# 153-03D_LCNC_IO_expander.net
KiCad netlist of a schematic drawn in EAGLE
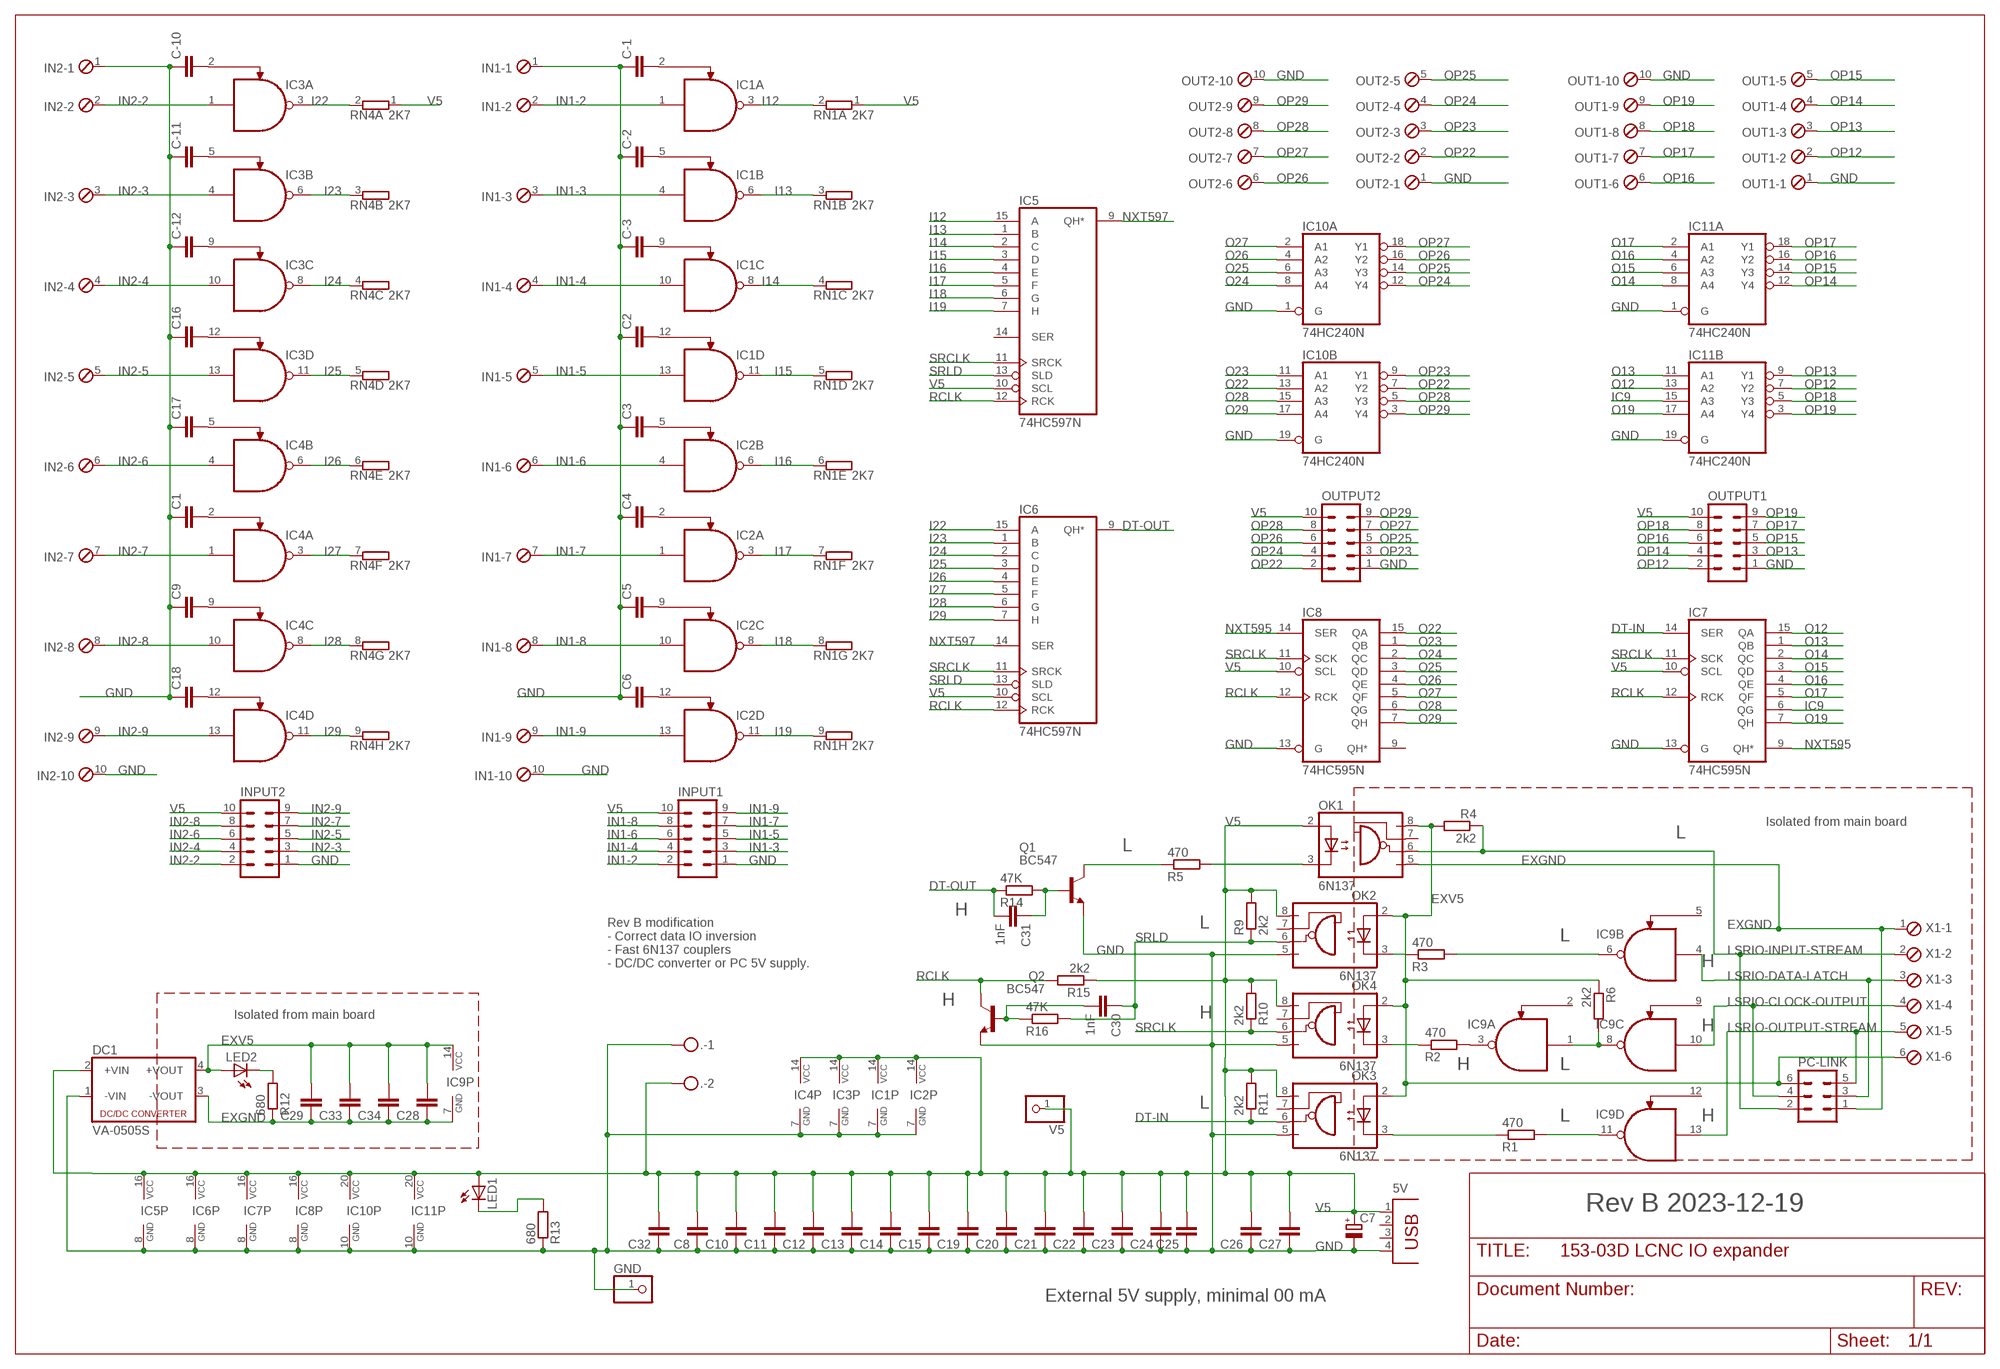
[diagram p0: schematic, sheet 1]

(export (version "E")
  (design (tool "Eeschema 10.0.6"))
  (components
    (comp (ref ".")
      (value "MKDSN1,5/2-5,08")
      (footprint "eagle-import:MKDSN1,5_2-5,08")
      (libsource (lib "eagle-import") (part "MKDSN1,5/2-5,08"))
    )
    (comp (ref "5V")
      (value "PN87520")
      (footprint "eagle-import:PN87520")
      (libsource (lib "eagle-import") (part "PN87520"))
    )
    (comp (ref "C-1")
      (value "C-EU025-024X044")
      (footprint "eagle-import:C025-024X044")
      (libsource (lib "eagle-import") (part "C-EU025-024X044"))
    )
    (comp (ref "C-2")
      (value "C-EU025-024X044")
      (footprint "eagle-import:C025-024X044")
      (libsource (lib "eagle-import") (part "C-EU025-024X044"))
    )
    (comp (ref "C-3")
      (value "C-EU025-024X044")
      (footprint "eagle-import:C025-024X044")
      (libsource (lib "eagle-import") (part "C-EU025-024X044"))
    )
    (comp (ref "C-10")
      (value "C-EU025-024X044")
      (footprint "eagle-import:C025-024X044")
      (libsource (lib "eagle-import") (part "C-EU025-024X044"))
    )
    (comp (ref "C-11")
      (value "C-EU025-024X044")
      (footprint "eagle-import:C025-024X044")
      (libsource (lib "eagle-import") (part "C-EU025-024X044"))
    )
    (comp (ref "C-12")
      (value "C-EU025-024X044")
      (footprint "eagle-import:C025-024X044")
      (libsource (lib "eagle-import") (part "C-EU025-024X044"))
    )
    (comp (ref "C1")
      (value "C-EU025-024X044")
      (footprint "eagle-import:C025-024X044")
      (libsource (lib "eagle-import") (part "C-EU025-024X044"))
    )
    (comp (ref "C2")
      (value "C-EU025-024X044")
      (footprint "eagle-import:C025-024X044")
      (libsource (lib "eagle-import") (part "C-EU025-024X044"))
    )
    (comp (ref "C3")
      (value "C-EU025-024X044")
      (footprint "eagle-import:C025-024X044")
      (libsource (lib "eagle-import") (part "C-EU025-024X044"))
    )
    (comp (ref "C4")
      (value "C-EU025-024X044")
      (footprint "eagle-import:C025-024X044")
      (libsource (lib "eagle-import") (part "C-EU025-024X044"))
    )
    (comp (ref "C5")
      (value "C-EU025-024X044")
      (footprint "eagle-import:C025-024X044")
      (libsource (lib "eagle-import") (part "C-EU025-024X044"))
    )
    (comp (ref "C6")
      (value "C-EU025-024X044")
      (footprint "eagle-import:C025-024X044")
      (libsource (lib "eagle-import") (part "C-EU025-024X044"))
    )
    (comp (ref "C7")
      (value "CPOL-EUE3.5-8")
      (footprint "eagle-import:E3,5-8")
      (libsource (lib "eagle-import") (part "CPOL-EUE3.5-8"))
    )
    (comp (ref "C8")
      (value "C-EU025-024X044")
      (footprint "eagle-import:C025-024X044")
      (libsource (lib "eagle-import") (part "C-EU025-024X044"))
    )
    (comp (ref "C9")
      (value "C-EU025-024X044")
      (footprint "eagle-import:C025-024X044")
      (libsource (lib "eagle-import") (part "C-EU025-024X044"))
    )
    (comp (ref "C10")
      (value "C-EU025-024X044")
      (footprint "eagle-import:C025-024X044")
      (libsource (lib "eagle-import") (part "C-EU025-024X044"))
    )
    (comp (ref "C11")
      (value "C-EU025-024X044")
      (footprint "eagle-import:C025-024X044")
      (libsource (lib "eagle-import") (part "C-EU025-024X044"))
    )
    (comp (ref "C12")
      (value "C-EU025-024X044")
      (footprint "eagle-import:C025-024X044")
      (libsource (lib "eagle-import") (part "C-EU025-024X044"))
    )
    (comp (ref "C13")
      (value "C-EU025-024X044")
      (footprint "eagle-import:C025-024X044")
      (libsource (lib "eagle-import") (part "C-EU025-024X044"))
    )
    (comp (ref "C14")
      (value "C-EU025-024X044")
      (footprint "eagle-import:C025-024X044")
      (libsource (lib "eagle-import") (part "C-EU025-024X044"))
    )
    (comp (ref "C15")
      (value "C-EU025-024X044")
      (footprint "eagle-import:C025-024X044")
      (libsource (lib "eagle-import") (part "C-EU025-024X044"))
    )
    (comp (ref "C16")
      (value "C-EU025-024X044")
      (footprint "eagle-import:C025-024X044")
      (libsource (lib "eagle-import") (part "C-EU025-024X044"))
    )
    (comp (ref "C17")
      (value "C-EU025-024X044")
      (footprint "eagle-import:C025-024X044")
      (libsource (lib "eagle-import") (part "C-EU025-024X044"))
    )
    (comp (ref "C18")
      (value "C-EU025-024X044")
      (footprint "eagle-import:C025-024X044")
      (libsource (lib "eagle-import") (part "C-EU025-024X044"))
    )
    (comp (ref "C19")
      (value "C-EU025-024X044")
      (footprint "eagle-import:C025-024X044")
      (libsource (lib "eagle-import") (part "C-EU025-024X044"))
    )
    (comp (ref "C20")
      (value "C-EU025-024X044")
      (footprint "eagle-import:C025-024X044")
      (libsource (lib "eagle-import") (part "C-EU025-024X044"))
    )
    (comp (ref "C21")
      (value "C-EU025-024X044")
      (footprint "eagle-import:C025-024X044")
      (libsource (lib "eagle-import") (part "C-EU025-024X044"))
    )
    (comp (ref "C22")
      (value "C-EU025-024X044")
      (footprint "eagle-import:C025-024X044")
      (libsource (lib "eagle-import") (part "C-EU025-024X044"))
    )
    (comp (ref "C23")
      (value "C-EU025-024X044")
      (footprint "eagle-import:C025-024X044")
      (libsource (lib "eagle-import") (part "C-EU025-024X044"))
    )
    (comp (ref "C24")
      (value "C-EU025-024X044")
      (footprint "eagle-import:C025-024X044")
      (libsource (lib "eagle-import") (part "C-EU025-024X044"))
    )
    (comp (ref "C25")
      (value "C-EU025-024X044")
      (footprint "eagle-import:C025-024X044")
      (libsource (lib "eagle-import") (part "C-EU025-024X044"))
    )
    (comp (ref "C26")
      (value "C-EU025-024X044")
      (footprint "eagle-import:C025-024X044")
      (libsource (lib "eagle-import") (part "C-EU025-024X044"))
    )
    (comp (ref "C27")
      (value "C-EU025-024X044")
      (footprint "eagle-import:C025-024X044")
      (libsource (lib "eagle-import") (part "C-EU025-024X044"))
    )
    (comp (ref "C28")
      (value "C-EU025-024X044")
      (footprint "eagle-import:C025-024X044")
      (libsource (lib "eagle-import") (part "C-EU025-024X044"))
    )
    (comp (ref "C29")
      (value "C-EU025-024X044")
      (footprint "eagle-import:C025-024X044")
      (libsource (lib "eagle-import") (part "C-EU025-024X044"))
    )
    (comp (ref "C30")
      (value "1nF")
      (footprint "eagle-import:C025-024X044")
      (libsource (lib "eagle-import") (part "C-EU025-024X044"))
    )
    (comp (ref "C31")
      (value "1nF")
      (footprint "eagle-import:C025-024X044")
      (libsource (lib "eagle-import") (part "C-EU025-024X044"))
    )
    (comp (ref "C32")
      (value "C-EU025-024X044")
      (footprint "eagle-import:C025-024X044")
      (libsource (lib "eagle-import") (part "C-EU025-024X044"))
    )
    (comp (ref "C33")
      (value "C-EU025-024X044")
      (footprint "eagle-import:C025-024X044")
      (libsource (lib "eagle-import") (part "C-EU025-024X044"))
    )
    (comp (ref "C34")
      (value "C-EU025-024X044")
      (footprint "eagle-import:C025-024X044")
      (libsource (lib "eagle-import") (part "C-EU025-024X044"))
    )
    (comp (ref "DC1")
      (value "VA-0505S")
      (footprint "eagle-import:4SIL")
      (libsource (lib "eagle-import") (part "VA-?S0505"))
    )
    (comp (ref "GND")
      (value "PINHD-1X1")
      (footprint "eagle-import:1X01")
      (libsource (lib "eagle-import") (part "PINHD-1X1"))
    )
    (comp (ref "IC1")
      (value "MC1489DIP")
      (footprint "eagle-import:DIL14")
      (libsource (lib "eagle-import") (part "MC1489DIP"))
    )
    (comp (ref "IC2")
      (value "MC1489DIP")
      (footprint "eagle-import:DIL14")
      (libsource (lib "eagle-import") (part "MC1489DIP"))
    )
    (comp (ref "IC3")
      (value "MC1489DIP")
      (footprint "eagle-import:DIL14")
      (libsource (lib "eagle-import") (part "MC1489DIP"))
    )
    (comp (ref "IC4")
      (value "MC1489DIP")
      (footprint "eagle-import:DIL14")
      (libsource (lib "eagle-import") (part "MC1489DIP"))
    )
    (comp (ref "IC5")
      (value "74HC597N")
      (footprint "eagle-import:DIL16")
      (libsource (lib "eagle-import") (part "74597NHC"))
    )
    (comp (ref "IC6")
      (value "74HC597N")
      (footprint "eagle-import:DIL16")
      (libsource (lib "eagle-import") (part "74597NHC"))
    )
    (comp (ref "IC7")
      (value "74HC595N")
      (footprint "eagle-import:DIL16")
      (libsource (lib "eagle-import") (part "74595NHC"))
    )
    (comp (ref "IC8")
      (value "74HC595N")
      (footprint "eagle-import:DIL16")
      (libsource (lib "eagle-import") (part "74595NHC"))
    )
    (comp (ref "IC9")
      (value "MC1489DIP")
      (footprint "eagle-import:DIL14")
      (libsource (lib "eagle-import") (part "MC1489DIP"))
    )
    (comp (ref "IC10")
      (value "74HC240N")
      (footprint "eagle-import:DIL20")
      (libsource (lib "eagle-import") (part "74240NHC"))
    )
    (comp (ref "IC11")
      (value "74HC240N")
      (footprint "eagle-import:DIL20")
      (libsource (lib "eagle-import") (part "74240NHC"))
    )
    (comp (ref "IN1")
      (value "MPT10")
      (footprint "eagle-import:10POL254")
      (libsource (lib "eagle-import") (part "MPT10"))
    )
    (comp (ref "IN2")
      (value "MPT10")
      (footprint "eagle-import:10POL254")
      (libsource (lib "eagle-import") (part "MPT10"))
    )
    (comp (ref "INPUT1")
      (value "ML10")
      (footprint "eagle-import:ML10")
      (libsource (lib "eagle-import") (part "ML10"))
    )
    (comp (ref "INPUT2")
      (value "ML10")
      (footprint "eagle-import:ML10")
      (libsource (lib "eagle-import") (part "ML10"))
    )
    (comp (ref "LED1")
      (value "LED3MM")
      (footprint "eagle-import:LED3MM")
      (libsource (lib "eagle-import") (part "LED3MM"))
    )
    (comp (ref "LED2")
      (value "LED3MM")
      (footprint "eagle-import:LED3MM")
      (libsource (lib "eagle-import") (part "LED3MM"))
    )
    (comp (ref "OK1")
      (value "6N137")
      (footprint "eagle-import:DIL08")
      (libsource (lib "eagle-import") (part "6N137"))
    )
    (comp (ref "OK2")
      (value "6N137")
      (footprint "eagle-import:DIL08")
      (libsource (lib "eagle-import") (part "6N137"))
    )
    (comp (ref "OK3")
      (value "6N137")
      (footprint "eagle-import:DIL08")
      (libsource (lib "eagle-import") (part "6N137"))
    )
    (comp (ref "OK4")
      (value "6N137")
      (footprint "eagle-import:DIL08")
      (libsource (lib "eagle-import") (part "6N137"))
    )
    (comp (ref "OUT1")
      (value "MPT10")
      (footprint "eagle-import:10POL254")
      (libsource (lib "eagle-import") (part "MPT10"))
    )
    (comp (ref "OUT2")
      (value "MPT10")
      (footprint "eagle-import:10POL254")
      (libsource (lib "eagle-import") (part "MPT10"))
    )
    (comp (ref "OUTPUT1")
      (value "ML10")
      (footprint "eagle-import:ML10")
      (libsource (lib "eagle-import") (part "ML10"))
    )
    (comp (ref "OUTPUT2")
      (value "ML10")
      (footprint "eagle-import:ML10")
      (libsource (lib "eagle-import") (part "ML10"))
    )
    (comp (ref "PC-LINK")
      (value "ML6")
      (footprint "eagle-import:ML6")
      (libsource (lib "eagle-import") (part "ML6"))
    )
    (comp (ref "Q1")
      (value "BC547")
      (footprint "eagle-import:TO92")
      (libsource (lib "eagle-import") (part "BC547"))
    )
    (comp (ref "Q2")
      (value "BC547")
      (footprint "eagle-import:TO92")
      (libsource (lib "eagle-import") (part "BC547"))
    )
    (comp (ref "R1")
      (value "470")
      (footprint "eagle-import:0207_10")
      (libsource (lib "eagle-import") (part "R-EU_0207/10"))
    )
    (comp (ref "R2")
      (value "470")
      (footprint "eagle-import:0207_10")
      (libsource (lib "eagle-import") (part "R-EU_0207/10"))
    )
    (comp (ref "R3")
      (value "470")
      (footprint "eagle-import:0207_10")
      (libsource (lib "eagle-import") (part "R-EU_0207/10"))
    )
    (comp (ref "R4")
      (value "2k2")
      (footprint "eagle-import:0207_10")
      (libsource (lib "eagle-import") (part "R-EU_0207/10"))
    )
    (comp (ref "R5")
      (value "470")
      (footprint "eagle-import:0207_10")
      (libsource (lib "eagle-import") (part "R-EU_0207/10"))
    )
    (comp (ref "R6")
      (value "2k2")
      (footprint "eagle-import:0207_10")
      (libsource (lib "eagle-import") (part "R-EU_0207/10"))
    )
    (comp (ref "R9")
      (value "2k2")
      (footprint "eagle-import:0207_10")
      (libsource (lib "eagle-import") (part "R-EU_0207/10"))
    )
    (comp (ref "R10")
      (value "2k2")
      (footprint "eagle-import:0207_10")
      (libsource (lib "eagle-import") (part "R-EU_0207/10"))
    )
    (comp (ref "R11")
      (value "2k2")
      (footprint "eagle-import:0207_10")
      (libsource (lib "eagle-import") (part "R-EU_0207/10"))
    )
    (comp (ref "R12")
      (value "680")
      (footprint "eagle-import:0207_10")
      (libsource (lib "eagle-import") (part "R-EU_0207/10"))
    )
    (comp (ref "R13")
      (value "680")
      (footprint "eagle-import:0207_10")
      (libsource (lib "eagle-import") (part "R-EU_0207/10"))
    )
    (comp (ref "R14")
      (value "47K")
      (footprint "eagle-import:0207_10")
      (libsource (lib "eagle-import") (part "R-EU_0207/10"))
    )
    (comp (ref "R15")
      (value "2k2")
      (footprint "eagle-import:0207_10")
      (libsource (lib "eagle-import") (part "R-EU_0207/10"))
    )
    (comp (ref "R16")
      (value "47K")
      (footprint "eagle-import:0207_10")
      (libsource (lib "eagle-import") (part "R-EU_0207/10"))
    )
    (comp (ref "RN1")
      (value "2K7")
      (footprint "eagle-import:SIL9")
      (libsource (lib "eagle-import") (part "GE08R"))
    )
    (comp (ref "RN4")
      (value "2K7")
      (footprint "eagle-import:SIL9")
      (libsource (lib "eagle-import") (part "GE08R"))
    )
    (comp (ref "V5")
      (value "PINHD-1X1")
      (footprint "eagle-import:1X01")
      (libsource (lib "eagle-import") (part "PINHD-1X1"))
    )
    (comp (ref "X1")
      (value "MPT6")
      (footprint "eagle-import:6POL254")
      (libsource (lib "eagle-import") (part "MPT6"))
    )
  )
  (nets
    (net (code "1") (name "/DT-IN") (class "Default")
      (node (ref "IC7") (pin "14") (pinfunction "SER_14") (pintype "input"))
      (node (ref "OK3") (pin "6") (pinfunction "VO_6") (pintype "passive"))
      (node (ref "R11") (pin "1") (pinfunction "1_1") (pintype "passive"))
    )
    (net (code "2") (name "/DT-OUT") (class "Default")
      (node (ref "C31") (pin "2") (pinfunction "2_2") (pintype "passive"))
      (node (ref "IC6") (pin "9") (pinfunction "QH*_9") (pintype "output"))
      (node (ref "R14") (pin "1") (pinfunction "1_1") (pintype "passive"))
    )
    (net (code "3") (name "/EXGND") (class "Default")
      (node (ref "C28") (pin "1") (pinfunction "1_1") (pintype "passive"))
      (node (ref "C29") (pin "1") (pinfunction "1_1") (pintype "passive"))
      (node (ref "C33") (pin "1") (pinfunction "1_1") (pintype "passive"))
      (node (ref "C34") (pin "1") (pinfunction "1_1") (pintype "passive"))
      (node (ref "DC1") (pin "3") (pinfunction "-VOUT_3") (pintype "passive"))
      (node (ref "IC9") (pin "7") (pinfunction "GND_7") (pintype "power_in"))
      (node (ref "OK1") (pin "5") (pinfunction "GND_5") (pintype "passive"))
      (node (ref "PC-LINK") (pin "1") (pinfunction "1_1") (pintype "passive"))
      (node (ref "R12") (pin "1") (pinfunction "1_1") (pintype "passive"))
      (node (ref "X1") (pin "1") (pinfunction "1_1") (pintype "passive"))
    )
    (net (code "4") (name "/EXV5") (class "Default")
      (node (ref "C28") (pin "2") (pinfunction "2_2") (pintype "passive"))
      (node (ref "C29") (pin "2") (pinfunction "2_2") (pintype "passive"))
      (node (ref "C33") (pin "2") (pinfunction "2_2") (pintype "passive"))
      (node (ref "C34") (pin "2") (pinfunction "2_2") (pintype "passive"))
      (node (ref "DC1") (pin "4") (pinfunction "+VOUT_4") (pintype "passive"))
      (node (ref "IC9") (pin "14") (pinfunction "VCC_14") (pintype "power_in"))
      (node (ref "LED2") (pin "A") (pinfunction "A_A") (pintype "passive"))
      (node (ref "OK1") (pin "8") (pinfunction "VCC_8") (pintype "passive"))
      (node (ref "OK2") (pin "2") (pinfunction "A_2") (pintype "passive"))
      (node (ref "OK3") (pin "2") (pinfunction "A_2") (pintype "passive"))
      (node (ref "OK4") (pin "2") (pinfunction "A_2") (pintype "passive"))
      (node (ref "PC-LINK") (pin "6") (pinfunction "6_6") (pintype "passive"))
      (node (ref "R4") (pin "2") (pinfunction "2_2") (pintype "passive"))
      (node (ref "R6") (pin "1") (pinfunction "1_1") (pintype "passive"))
      (node (ref "X1") (pin "6") (pinfunction "1_6") (pintype "passive"))
    )
    (net (code "5") (name "/GND") (class "Default")
      (node (ref ".") (pin "1") (pinfunction "KL_1") (pintype "passive"))
      (node (ref "5V") (pin "4") (pinfunction "4_4") (pintype "passive"))
      (node (ref "C-1") (pin "1") (pinfunction "1_1") (pintype "passive"))
      (node (ref "C-10") (pin "1") (pinfunction "1_1") (pintype "passive"))
      (node (ref "C-11") (pin "1") (pinfunction "1_1") (pintype "passive"))
      (node (ref "C-12") (pin "1") (pinfunction "1_1") (pintype "passive"))
      (node (ref "C-2") (pin "1") (pinfunction "1_1") (pintype "passive"))
      (node (ref "C-3") (pin "1") (pinfunction "1_1") (pintype "passive"))
      (node (ref "C1") (pin "1") (pinfunction "1_1") (pintype "passive"))
      (node (ref "C10") (pin "1") (pinfunction "1_1") (pintype "passive"))
      (node (ref "C11") (pin "1") (pinfunction "1_1") (pintype "passive"))
      (node (ref "C12") (pin "1") (pinfunction "1_1") (pintype "passive"))
      (node (ref "C13") (pin "1") (pinfunction "1_1") (pintype "passive"))
      (node (ref "C14") (pin "1") (pinfunction "1_1") (pintype "passive"))
      (node (ref "C15") (pin "1") (pinfunction "1_1") (pintype "passive"))
      (node (ref "C16") (pin "1") (pinfunction "1_1") (pintype "passive"))
      (node (ref "C17") (pin "1") (pinfunction "1_1") (pintype "passive"))
      (node (ref "C18") (pin "1") (pinfunction "1_1") (pintype "passive"))
      (node (ref "C19") (pin "1") (pinfunction "1_1") (pintype "passive"))
      (node (ref "C2") (pin "1") (pinfunction "1_1") (pintype "passive"))
      (node (ref "C20") (pin "1") (pinfunction "1_1") (pintype "passive"))
      (node (ref "C21") (pin "1") (pinfunction "1_1") (pintype "passive"))
      (node (ref "C22") (pin "1") (pinfunction "1_1") (pintype "passive"))
      (node (ref "C23") (pin "1") (pinfunction "1_1") (pintype "passive"))
      (node (ref "C24") (pin "1") (pinfunction "1_1") (pintype "passive"))
      (node (ref "C25") (pin "1") (pinfunction "1_1") (pintype "passive"))
      (node (ref "C26") (pin "1") (pinfunction "1_1") (pintype "passive"))
      (node (ref "C27") (pin "1") (pinfunction "1_1") (pintype "passive"))
      (node (ref "C3") (pin "1") (pinfunction "1_1") (pintype "passive"))
      (node (ref "C32") (pin "1") (pinfunction "1_1") (pintype "passive"))
      (node (ref "C4") (pin "1") (pinfunction "1_1") (pintype "passive"))
      (node (ref "C5") (pin "1") (pinfunction "1_1") (pintype "passive"))
      (node (ref "C6") (pin "1") (pinfunction "1_1") (pintype "passive"))
      (node (ref "C7") (pin "-") (pinfunction "-_-") (pintype "passive"))
      (node (ref "C8") (pin "1") (pinfunction "1_1") (pintype "passive"))
      (node (ref "C9") (pin "1") (pinfunction "1_1") (pintype "passive"))
      (node (ref "DC1") (pin "1") (pinfunction "-VIN_1") (pintype "passive"))
      (node (ref "GND") (pin "1") (pinfunction "1_1") (pintype "passive"))
      (node (ref "IC1") (pin "7") (pinfunction "GND_7") (pintype "power_in"))
      (node (ref "IC10") (pin "1") (pinfunction "G_1") (pintype "input"))
      (node (ref "IC10") (pin "10") (pinfunction "GND_10") (pintype "power_in"))
      (node (ref "IC10") (pin "19") (pinfunction "G_19") (pintype "input"))
      (node (ref "IC11") (pin "1") (pinfunction "G_1") (pintype "input"))
      (node (ref "IC11") (pin "10") (pinfunction "GND_10") (pintype "power_in"))
      (node (ref "IC11") (pin "19") (pinfunction "G_19") (pintype "input"))
      (node (ref "IC2") (pin "7") (pinfunction "GND_7") (pintype "power_in"))
      (node (ref "IC3") (pin "7") (pinfunction "GND_7") (pintype "power_in"))
      (node (ref "IC4") (pin "7") (pinfunction "GND_7") (pintype "power_in"))
      (node (ref "IC5") (pin "8") (pinfunction "GND_8") (pintype "power_in"))
      (node (ref "IC6") (pin "8") (pinfunction "GND_8") (pintype "power_in"))
      (node (ref "IC7") (pin "13") (pinfunction "G_13") (pintype "input"))
      (node (ref "IC7") (pin "8") (pinfunction "GND_8") (pintype "power_in"))
      (node (ref "IC8") (pin "13") (pinfunction "G_13") (pintype "input"))
      (node (ref "IC8") (pin "8") (pinfunction "GND_8") (pintype "power_in"))
      (node (ref "IN1") (pin "1") (pinfunction "1_1") (pintype "passive"))
      (node (ref "IN1") (pin "10") (pinfunction "1_10") (pintype "passive"))
      (node (ref "IN2") (pin "1") (pinfunction "1_1") (pintype "passive"))
      (node (ref "IN2") (pin "10") (pinfunction "1_10") (pintype "passive"))
      (node (ref "INPUT1") (pin "1") (pinfunction "1_1") (pintype "passive"))
      (node (ref "INPUT2") (pin "1") (pinfunction "1_1") (pintype "passive"))
      (node (ref "OK2") (pin "5") (pinfunction "GND_5") (pintype "passive"))
      (node (ref "OK3") (pin "5") (pinfunction "GND_5") (pintype "passive"))
      (node (ref "OK4") (pin "5") (pinfunction "GND_5") (pintype "passive"))
      (node (ref "OUT1") (pin "1") (pinfunction "1_1") (pintype "passive"))
      (node (ref "OUT1") (pin "10") (pinfunction "1_10") (pintype "passive"))
      (node (ref "OUT2") (pin "1") (pinfunction "1_1") (pintype "passive"))
      (node (ref "OUT2") (pin "10") (pinfunction "1_10") (pintype "passive"))
      (node (ref "OUTPUT1") (pin "1") (pinfunction "1_1") (pintype "passive"))
      (node (ref "OUTPUT2") (pin "1") (pinfunction "1_1") (pintype "passive"))
      (node (ref "Q1") (pin "1") (pinfunction "E_1") (pintype "passive"))
      (node (ref "Q2") (pin "1") (pinfunction "E_1") (pintype "passive"))
      (node (ref "R13") (pin "1") (pinfunction "1_1") (pintype "passive"))
    )
    (net (code "6") (name "/I12") (class "Default")
      (node (ref "IC1") (pin "3") (pinfunction "O_3") (pintype "output"))
      (node (ref "IC5") (pin "15") (pinfunction "A_15") (pintype "input"))
      (node (ref "RN1") (pin "2") (pinfunction "2_2") (pintype "passive"))
    )
    (net (code "7") (name "/I13") (class "Default")
      (node (ref "IC1") (pin "6") (pinfunction "O_6") (pintype "output"))
      (node (ref "IC5") (pin "1") (pinfunction "B_1") (pintype "input"))
      (node (ref "RN1") (pin "3") (pinfunction "2_3") (pintype "passive"))
    )
    (net (code "8") (name "/I14") (class "Default")
      (node (ref "IC1") (pin "8") (pinfunction "O_8") (pintype "output"))
      (node (ref "IC5") (pin "2") (pinfunction "C_2") (pintype "input"))
      (node (ref "RN1") (pin "4") (pinfunction "2_4") (pintype "passive"))
    )
    (net (code "9") (name "/I15") (class "Default")
      (node (ref "IC1") (pin "11") (pinfunction "O_11") (pintype "output"))
      (node (ref "IC5") (pin "3") (pinfunction "D_3") (pintype "input"))
      (node (ref "RN1") (pin "5") (pinfunction "2_5") (pintype "passive"))
    )
    (net (code "10") (name "/I16") (class "Default")
      (node (ref "IC2") (pin "6") (pinfunction "O_6") (pintype "output"))
      (node (ref "IC5") (pin "4") (pinfunction "E_4") (pintype "input"))
      (node (ref "RN1") (pin "6") (pinfunction "2_6") (pintype "passive"))
    )
    (net (code "11") (name "/I17") (class "Default")
      (node (ref "IC2") (pin "3") (pinfunction "O_3") (pintype "output"))
      (node (ref "IC5") (pin "5") (pinfunction "F_5") (pintype "input"))
      (node (ref "RN1") (pin "7") (pinfunction "2_7") (pintype "passive"))
    )
    (net (code "12") (name "/I18") (class "Default")
      (node (ref "IC2") (pin "8") (pinfunction "O_8") (pintype "output"))
      (node (ref "IC5") (pin "6") (pinfunction "G_6") (pintype "input"))
      (node (ref "RN1") (pin "8") (pinfunction "2_8") (pintype "passive"))
    )
    (net (code "13") (name "/I19") (class "Default")
      (node (ref "IC2") (pin "11") (pinfunction "O_11") (pintype "output"))
      (node (ref "IC5") (pin "7") (pinfunction "H_7") (pintype "input"))
      (node (ref "RN1") (pin "9") (pinfunction "2_9") (pintype "passive"))
    )
    (net (code "14") (name "/I22") (class "Default")
      (node (ref "IC3") (pin "3") (pinfunction "O_3") (pintype "output"))
      (node (ref "IC6") (pin "15") (pinfunction "A_15") (pintype "input"))
      (node (ref "RN4") (pin "2") (pinfunction "2_2") (pintype "passive"))
    )
    (net (code "15") (name "/I23") (class "Default")
      (node (ref "IC3") (pin "6") (pinfunction "O_6") (pintype "output"))
      (node (ref "IC6") (pin "1") (pinfunction "B_1") (pintype "input"))
      (node (ref "RN4") (pin "3") (pinfunction "2_3") (pintype "passive"))
    )
    (net (code "16") (name "/I24") (class "Default")
      (node (ref "IC3") (pin "8") (pinfunction "O_8") (pintype "output"))
      (node (ref "IC6") (pin "2") (pinfunction "C_2") (pintype "input"))
      (node (ref "RN4") (pin "4") (pinfunction "2_4") (pintype "passive"))
    )
    (net (code "17") (name "/I25") (class "Default")
      (node (ref "IC3") (pin "11") (pinfunction "O_11") (pintype "output"))
      (node (ref "IC6") (pin "3") (pinfunction "D_3") (pintype "input"))
      (node (ref "RN4") (pin "5") (pinfunction "2_5") (pintype "passive"))
    )
    (net (code "18") (name "/I26") (class "Default")
      (node (ref "IC4") (pin "6") (pinfunction "O_6") (pintype "output"))
      (node (ref "IC6") (pin "4") (pinfunction "E_4") (pintype "input"))
      (node (ref "RN4") (pin "6") (pinfunction "2_6") (pintype "passive"))
    )
    (net (code "19") (name "/I27") (class "Default")
      (node (ref "IC4") (pin "3") (pinfunction "O_3") (pintype "output"))
      (node (ref "IC6") (pin "5") (pinfunction "F_5") (pintype "input"))
      (node (ref "RN4") (pin "7") (pinfunction "2_7") (pintype "passive"))
    )
    (net (code "20") (name "/I28") (class "Default")
      (node (ref "IC4") (pin "8") (pinfunction "O_8") (pintype "output"))
      (node (ref "IC6") (pin "6") (pinfunction "G_6") (pintype "input"))
      (node (ref "RN4") (pin "8") (pinfunction "2_8") (pintype "passive"))
    )
    (net (code "21") (name "/I29") (class "Default")
      (node (ref "IC4") (pin "11") (pinfunction "O_11") (pintype "output"))
      (node (ref "IC6") (pin "7") (pinfunction "H_7") (pintype "input"))
      (node (ref "RN4") (pin "9") (pinfunction "2_9") (pintype "passive"))
    )
    (net (code "22") (name "/IC9") (class "Default")
      (node (ref "IC11") (pin "15") (pinfunction "A3_15") (pintype "input"))
      (node (ref "IC7") (pin "6") (pinfunction "QG_6") (pintype "tri_state"))
    )
    (net (code "23") (name "/IN1-2") (class "Default")
      (node (ref "IC1") (pin "1") (pinfunction "I0_1") (pintype "input"))
      (node (ref "IN1") (pin "2") (pinfunction "1_2") (pintype "passive"))
      (node (ref "INPUT1") (pin "2") (pinfunction "2_2") (pintype "passive"))
    )
    (net (code "24") (name "/IN1-3") (class "Default")
      (node (ref "IC1") (pin "4") (pinfunction "I0_4") (pintype "input"))
      (node (ref "IN1") (pin "3") (pinfunction "1_3") (pintype "passive"))
      (node (ref "INPUT1") (pin "3") (pinfunction "3_3") (pintype "passive"))
    )
    (net (code "25") (name "/IN1-4") (class "Default")
      (node (ref "IC1") (pin "10") (pinfunction "I0_10") (pintype "input"))
      (node (ref "IN1") (pin "4") (pinfunction "1_4") (pintype "passive"))
      (node (ref "INPUT1") (pin "4") (pinfunction "4_4") (pintype "passive"))
    )
    (net (code "26") (name "/IN1-5") (class "Default")
      (node (ref "IC1") (pin "13") (pinfunction "I0_13") (pintype "input"))
      (node (ref "IN1") (pin "5") (pinfunction "1_5") (pintype "passive"))
      (node (ref "INPUT1") (pin "5") (pinfunction "5_5") (pintype "passive"))
    )
    (net (code "27") (name "/IN1-6") (class "Default")
      (node (ref "IC2") (pin "4") (pinfunction "I0_4") (pintype "input"))
      (node (ref "IN1") (pin "6") (pinfunction "1_6") (pintype "passive"))
      (node (ref "INPUT1") (pin "6") (pinfunction "6_6") (pintype "passive"))
    )
    (net (code "28") (name "/IN1-7") (class "Default")
      (node (ref "IC2") (pin "1") (pinfunction "I0_1") (pintype "input"))
      (node (ref "IN1") (pin "7") (pinfunction "1_7") (pintype "passive"))
      (node (ref "INPUT1") (pin "7") (pinfunction "7_7") (pintype "passive"))
    )
    (net (code "29") (name "/IN1-8") (class "Default")
      (node (ref "IC2") (pin "10") (pinfunction "I0_10") (pintype "input"))
      (node (ref "IN1") (pin "8") (pinfunction "1_8") (pintype "passive"))
      (node (ref "INPUT1") (pin "8") (pinfunction "8_8") (pintype "passive"))
    )
    (net (code "30") (name "/IN1-9") (class "Default")
      (node (ref "IC2") (pin "13") (pinfunction "I0_13") (pintype "input"))
      (node (ref "IN1") (pin "9") (pinfunction "1_9") (pintype "passive"))
      (node (ref "INPUT1") (pin "9") (pinfunction "9_9") (pintype "passive"))
    )
    (net (code "31") (name "/IN2-2") (class "Default")
      (node (ref "IC3") (pin "1") (pinfunction "I0_1") (pintype "input"))
      (node (ref "IN2") (pin "2") (pinfunction "1_2") (pintype "passive"))
      (node (ref "INPUT2") (pin "2") (pinfunction "2_2") (pintype "passive"))
    )
    (net (code "32") (name "/IN2-3") (class "Default")
      (node (ref "IC3") (pin "4") (pinfunction "I0_4") (pintype "input"))
      (node (ref "IN2") (pin "3") (pinfunction "1_3") (pintype "passive"))
      (node (ref "INPUT2") (pin "3") (pinfunction "3_3") (pintype "passive"))
    )
    (net (code "33") (name "/IN2-4") (class "Default")
      (node (ref "IC3") (pin "10") (pinfunction "I0_10") (pintype "input"))
      (node (ref "IN2") (pin "4") (pinfunction "1_4") (pintype "passive"))
      (node (ref "INPUT2") (pin "4") (pinfunction "4_4") (pintype "passive"))
    )
    (net (code "34") (name "/IN2-5") (class "Default")
      (node (ref "IC3") (pin "13") (pinfunction "I0_13") (pintype "input"))
      (node (ref "IN2") (pin "5") (pinfunction "1_5") (pintype "passive"))
      (node (ref "INPUT2") (pin "5") (pinfunction "5_5") (pintype "passive"))
    )
    (net (code "35") (name "/IN2-6") (class "Default")
      (node (ref "IC4") (pin "4") (pinfunction "I0_4") (pintype "input"))
      (node (ref "IN2") (pin "6") (pinfunction "1_6") (pintype "passive"))
      (node (ref "INPUT2") (pin "6") (pinfunction "6_6") (pintype "passive"))
    )
    (net (code "36") (name "/IN2-7") (class "Default")
      (node (ref "IC4") (pin "1") (pinfunction "I0_1") (pintype "input"))
      (node (ref "IN2") (pin "7") (pinfunction "1_7") (pintype "passive"))
      (node (ref "INPUT2") (pin "7") (pinfunction "7_7") (pintype "passive"))
    )
    (net (code "37") (name "/IN2-8") (class "Default")
      (node (ref "IC4") (pin "10") (pinfunction "I0_10") (pintype "input"))
      (node (ref "IN2") (pin "8") (pinfunction "1_8") (pintype "passive"))
      (node (ref "INPUT2") (pin "8") (pinfunction "8_8") (pintype "passive"))
    )
    (net (code "38") (name "/IN2-9") (class "Default")
      (node (ref "IC4") (pin "13") (pinfunction "I0_13") (pintype "input"))
      (node (ref "IN2") (pin "9") (pinfunction "1_9") (pintype "passive"))
      (node (ref "INPUT2") (pin "9") (pinfunction "9_9") (pintype "passive"))
    )
    (net (code "39") (name "/LSRIO-CLOCK-OUTPUT") (class "Default")
      (node (ref "IC9") (pin "10") (pinfunction "I0_10") (pintype "input"))
      (node (ref "PC-LINK") (pin "4") (pinfunction "4_4") (pintype "passive"))
      (node (ref "X1") (pin "4") (pinfunction "1_4") (pintype "passive"))
    )
    (net (code "40") (name "/LSRIO-DATA-LATCH") (class "Default")
      (node (ref "IC9") (pin "4") (pinfunction "I0_4") (pintype "input"))
      (node (ref "PC-LINK") (pin "3") (pinfunction "3_3") (pintype "passive"))
      (node (ref "X1") (pin "3") (pinfunction "1_3") (pintype "passive"))
    )
    (net (code "41") (name "/LSRIO-INPUT-STREAM") (class "Default")
      (node (ref "OK1") (pin "6") (pinfunction "VO_6") (pintype "passive"))
      (node (ref "PC-LINK") (pin "2") (pinfunction "2_2") (pintype "passive"))
      (node (ref "R4") (pin "1") (pinfunction "1_1") (pintype "passive"))
      (node (ref "X1") (pin "2") (pinfunction "1_2") (pintype "passive"))
    )
    (net (code "42") (name "/LSRIO-OUTPUT-STREAM") (class "Default")
      (node (ref "IC9") (pin "13") (pinfunction "I0_13") (pintype "input"))
      (node (ref "PC-LINK") (pin "5") (pinfunction "5_5") (pintype "passive"))
      (node (ref "X1") (pin "5") (pinfunction "1_5") (pintype "passive"))
    )
    (net (code "43") (name "/NXT595") (class "Default")
      (node (ref "IC7") (pin "9") (pinfunction "QH*_9") (pintype "tri_state"))
      (node (ref "IC8") (pin "14") (pinfunction "SER_14") (pintype "input"))
    )
    (net (code "44") (name "/NXT597") (class "Default")
      (node (ref "IC5") (pin "9") (pinfunction "QH*_9") (pintype "output"))
      (node (ref "IC6") (pin "14") (pinfunction "SER_14") (pintype "input"))
    )
    (net (code "45") (name "/O12") (class "Default")
      (node (ref "IC11") (pin "13") (pinfunction "A2_13") (pintype "input"))
      (node (ref "IC7") (pin "15") (pinfunction "QA_15") (pintype "tri_state"))
    )
    (net (code "46") (name "/O13") (class "Default")
      (node (ref "IC11") (pin "11") (pinfunction "A1_11") (pintype "input"))
      (node (ref "IC7") (pin "1") (pinfunction "QB_1") (pintype "tri_state"))
    )
    (net (code "47") (name "/O14") (class "Default")
      (node (ref "IC11") (pin "8") (pinfunction "A4_8") (pintype "input"))
      (node (ref "IC7") (pin "2") (pinfunction "QC_2") (pintype "tri_state"))
    )
    (net (code "48") (name "/O15") (class "Default")
      (node (ref "IC11") (pin "6") (pinfunction "A3_6") (pintype "input"))
      (node (ref "IC7") (pin "3") (pinfunction "QD_3") (pintype "tri_state"))
    )
    (net (code "49") (name "/O16") (class "Default")
      (node (ref "IC11") (pin "4") (pinfunction "A2_4") (pintype "input"))
      (node (ref "IC7") (pin "4") (pinfunction "QE_4") (pintype "tri_state"))
    )
    (net (code "50") (name "/O17") (class "Default")
      (node (ref "IC11") (pin "2") (pinfunction "A1_2") (pintype "input"))
      (node (ref "IC7") (pin "5") (pinfunction "QF_5") (pintype "tri_state"))
    )
    (net (code "51") (name "/O19") (class "Default")
      (node (ref "IC11") (pin "17") (pinfunction "A4_17") (pintype "input"))
      (node (ref "IC7") (pin "7") (pinfunction "QH_7") (pintype "tri_state"))
    )
    (net (code "52") (name "/O22") (class "Default")
      (node (ref "IC10") (pin "13") (pinfunction "A2_13") (pintype "input"))
      (node (ref "IC8") (pin "15") (pinfunction "QA_15") (pintype "tri_state"))
    )
    (net (code "53") (name "/O23") (class "Default")
      (node (ref "IC10") (pin "11") (pinfunction "A1_11") (pintype "input"))
      (node (ref "IC8") (pin "1") (pinfunction "QB_1") (pintype "tri_state"))
    )
    (net (code "54") (name "/O24") (class "Default")
      (node (ref "IC10") (pin "8") (pinfunction "A4_8") (pintype "input"))
      (node (ref "IC8") (pin "2") (pinfunction "QC_2") (pintype "tri_state"))
    )
    (net (code "55") (name "/O25") (class "Default")
      (node (ref "IC10") (pin "6") (pinfunction "A3_6") (pintype "input"))
      (node (ref "IC8") (pin "3") (pinfunction "QD_3") (pintype "tri_state"))
    )
    (net (code "56") (name "/O26") (class "Default")
      (node (ref "IC10") (pin "4") (pinfunction "A2_4") (pintype "input"))
      (node (ref "IC8") (pin "4") (pinfunction "QE_4") (pintype "tri_state"))
    )
    (net (code "57") (name "/O27") (class "Default")
      (node (ref "IC10") (pin "2") (pinfunction "A1_2") (pintype "input"))
      (node (ref "IC8") (pin "5") (pinfunction "QF_5") (pintype "tri_state"))
    )
    (net (code "58") (name "/O28") (class "Default")
      (node (ref "IC10") (pin "15") (pinfunction "A3_15") (pintype "input"))
      (node (ref "IC8") (pin "6") (pinfunction "QG_6") (pintype "tri_state"))
    )
    (net (code "59") (name "/O29") (class "Default")
      (node (ref "IC10") (pin "17") (pinfunction "A4_17") (pintype "input"))
      (node (ref "IC8") (pin "7") (pinfunction "QH_7") (pintype "tri_state"))
    )
    (net (code "60") (name "/OP12") (class "Default")
      (node (ref "IC11") (pin "7") (pinfunction "Y2_7") (pintype "tri_state"))
      (node (ref "OUT1") (pin "2") (pinfunction "1_2") (pintype "passive"))
      (node (ref "OUTPUT1") (pin "2") (pinfunction "2_2") (pintype "passive"))
    )
    (net (code "61") (name "/OP13") (class "Default")
      (node (ref "IC11") (pin "9") (pinfunction "Y1_9") (pintype "tri_state"))
      (node (ref "OUT1") (pin "3") (pinfunction "1_3") (pintype "passive"))
      (node (ref "OUTPUT1") (pin "3") (pinfunction "3_3") (pintype "passive"))
    )
    (net (code "62") (name "/OP14") (class "Default")
      (node (ref "IC11") (pin "12") (pinfunction "Y4_12") (pintype "tri_state"))
      (node (ref "OUT1") (pin "4") (pinfunction "1_4") (pintype "passive"))
      (node (ref "OUTPUT1") (pin "4") (pinfunction "4_4") (pintype "passive"))
    )
    (net (code "63") (name "/OP15") (class "Default")
      (node (ref "IC11") (pin "14") (pinfunction "Y3_14") (pintype "tri_state"))
      (node (ref "OUT1") (pin "5") (pinfunction "1_5") (pintype "passive"))
      (node (ref "OUTPUT1") (pin "5") (pinfunction "5_5") (pintype "passive"))
    )
    (net (code "64") (name "/OP16") (class "Default")
      (node (ref "IC11") (pin "16") (pinfunction "Y2_16") (pintype "tri_state"))
      (node (ref "OUT1") (pin "6") (pinfunction "1_6") (pintype "passive"))
      (node (ref "OUTPUT1") (pin "6") (pinfunction "6_6") (pintype "passive"))
    )
    (net (code "65") (name "/OP17") (class "Default")
      (node (ref "IC11") (pin "18") (pinfunction "Y1_18") (pintype "tri_state"))
      (node (ref "OUT1") (pin "7") (pinfunction "1_7") (pintype "passive"))
      (node (ref "OUTPUT1") (pin "7") (pinfunction "7_7") (pintype "passive"))
    )
    (net (code "66") (name "/OP18") (class "Default")
      (node (ref "IC11") (pin "5") (pinfunction "Y3_5") (pintype "tri_state"))
      (node (ref "OUT1") (pin "8") (pinfunction "1_8") (pintype "passive"))
      (node (ref "OUTPUT1") (pin "8") (pinfunction "8_8") (pintype "passive"))
    )
    (net (code "67") (name "/OP19") (class "Default")
      (node (ref "IC11") (pin "3") (pinfunction "Y4_3") (pintype "tri_state"))
      (node (ref "OUT1") (pin "9") (pinfunction "1_9") (pintype "passive"))
      (node (ref "OUTPUT1") (pin "9") (pinfunction "9_9") (pintype "passive"))
    )
    (net (code "68") (name "/OP22") (class "Default")
      (node (ref "IC10") (pin "7") (pinfunction "Y2_7") (pintype "tri_state"))
      (node (ref "OUT2") (pin "2") (pinfunction "1_2") (pintype "passive"))
      (node (ref "OUTPUT2") (pin "2") (pinfunction "2_2") (pintype "passive"))
    )
    (net (code "69") (name "/OP23") (class "Default")
      (node (ref "IC10") (pin "9") (pinfunction "Y1_9") (pintype "tri_state"))
      (node (ref "OUT2") (pin "3") (pinfunction "1_3") (pintype "passive"))
      (node (ref "OUTPUT2") (pin "3") (pinfunction "3_3") (pintype "passive"))
    )
    (net (code "70") (name "/OP24") (class "Default")
      (node (ref "IC10") (pin "12") (pinfunction "Y4_12") (pintype "tri_state"))
      (node (ref "OUT2") (pin "4") (pinfunction "1_4") (pintype "passive"))
      (node (ref "OUTPUT2") (pin "4") (pinfunction "4_4") (pintype "passive"))
    )
    (net (code "71") (name "/OP25") (class "Default")
      (node (ref "IC10") (pin "14") (pinfunction "Y3_14") (pintype "tri_state"))
      (node (ref "OUT2") (pin "5") (pinfunction "1_5") (pintype "passive"))
      (node (ref "OUTPUT2") (pin "5") (pinfunction "5_5") (pintype "passive"))
    )
    (net (code "72") (name "/OP26") (class "Default")
      (node (ref "IC10") (pin "16") (pinfunction "Y2_16") (pintype "tri_state"))
      (node (ref "OUT2") (pin "6") (pinfunction "1_6") (pintype "passive"))
      (node (ref "OUTPUT2") (pin "6") (pinfunction "6_6") (pintype "passive"))
    )
    (net (code "73") (name "/OP27") (class "Default")
      (node (ref "IC10") (pin "18") (pinfunction "Y1_18") (pintype "tri_state"))
      (node (ref "OUT2") (pin "7") (pinfunction "1_7") (pintype "passive"))
      (node (ref "OUTPUT2") (pin "7") (pinfunction "7_7") (pintype "passive"))
    )
    (net (code "74") (name "/OP28") (class "Default")
      (node (ref "IC10") (pin "5") (pinfunction "Y3_5") (pintype "tri_state"))
      (node (ref "OUT2") (pin "8") (pinfunction "1_8") (pintype "passive"))
      (node (ref "OUTPUT2") (pin "8") (pinfunction "8_8") (pintype "passive"))
    )
    (net (code "75") (name "/OP29") (class "Default")
      (node (ref "IC10") (pin "3") (pinfunction "Y4_3") (pintype "tri_state"))
      (node (ref "OUT2") (pin "9") (pinfunction "1_9") (pintype "passive"))
      (node (ref "OUTPUT2") (pin "9") (pinfunction "9_9") (pintype "passive"))
    )
    (net (code "76") (name "/RCLK") (class "Default")
      (node (ref "IC5") (pin "12") (pinfunction "RCK_12") (pintype "input"))
      (node (ref "IC6") (pin "12") (pinfunction "RCK_12") (pintype "input"))
      (node (ref "IC7") (pin "12") (pinfunction "RCK_12") (pintype "input"))
      (node (ref "IC8") (pin "12") (pinfunction "RCK_12") (pintype "input"))
      (node (ref "Q2") (pin "3") (pinfunction "C_3") (pintype "passive"))
      (node (ref "R15") (pin "2") (pinfunction "2_2") (pintype "passive"))
    )
    (net (code "77") (name "/SRCLK") (class "Default")
      (node (ref "IC5") (pin "11") (pinfunction "SRCK_11") (pintype "input"))
      (node (ref "IC6") (pin "11") (pinfunction "SRCK_11") (pintype "input"))
      (node (ref "IC7") (pin "11") (pinfunction "SCK_11") (pintype "input"))
      (node (ref "IC8") (pin "11") (pinfunction "SCK_11") (pintype "input"))
      (node (ref "OK4") (pin "6") (pinfunction "VO_6") (pintype "passive"))
      (node (ref "R10") (pin "1") (pinfunction "1_1") (pintype "passive"))
    )
    (net (code "78") (name "/SRLD") (class "Default")
      (node (ref "C30") (pin "1") (pinfunction "1_1") (pintype "passive"))
      (node (ref "IC5") (pin "13") (pinfunction "SLD_13") (pintype "input"))
      (node (ref "IC6") (pin "13") (pinfunction "SLD_13") (pintype "input"))
      (node (ref "OK2") (pin "6") (pinfunction "VO_6") (pintype "passive"))
      (node (ref "R16") (pin "2") (pinfunction "2_2") (pintype "passive"))
      (node (ref "R9") (pin "1") (pinfunction "1_1") (pintype "passive"))
    )
    (net (code "79") (name "/V5") (class "Default")
      (node (ref ".") (pin "2") (pinfunction "KL_2") (pintype "passive"))
      (node (ref "5V") (pin "1") (pinfunction "1_1") (pintype "passive"))
      (node (ref "C10") (pin "2") (pinfunction "2_2") (pintype "passive"))
      (node (ref "C11") (pin "2") (pinfunction "2_2") (pintype "passive"))
      (node (ref "C12") (pin "2") (pinfunction "2_2") (pintype "passive"))
      (node (ref "C13") (pin "2") (pinfunction "2_2") (pintype "passive"))
      (node (ref "C14") (pin "2") (pinfunction "2_2") (pintype "passive"))
      (node (ref "C15") (pin "2") (pinfunction "2_2") (pintype "passive"))
      (node (ref "C19") (pin "2") (pinfunction "2_2") (pintype "passive"))
      (node (ref "C20") (pin "2") (pinfunction "2_2") (pintype "passive"))
      (node (ref "C21") (pin "2") (pinfunction "2_2") (pintype "passive"))
      (node (ref "C22") (pin "2") (pinfunction "2_2") (pintype "passive"))
      (node (ref "C23") (pin "2") (pinfunction "2_2") (pintype "passive"))
      (node (ref "C24") (pin "2") (pinfunction "2_2") (pintype "passive"))
      (node (ref "C25") (pin "2") (pinfunction "2_2") (pintype "passive"))
      (node (ref "C26") (pin "2") (pinfunction "2_2") (pintype "passive"))
      (node (ref "C27") (pin "2") (pinfunction "2_2") (pintype "passive"))
      (node (ref "C32") (pin "2") (pinfunction "2_2") (pintype "passive"))
      (node (ref "C7") (pin "+") (pinfunction "+_+") (pintype "passive"))
      (node (ref "C8") (pin "2") (pinfunction "2_2") (pintype "passive"))
      (node (ref "DC1") (pin "2") (pinfunction "+VIN_2") (pintype "passive"))
      (node (ref "IC1") (pin "14") (pinfunction "VCC_14") (pintype "power_in"))
      (node (ref "IC10") (pin "20") (pinfunction "VCC_20") (pintype "power_in"))
      (node (ref "IC11") (pin "20") (pinfunction "VCC_20") (pintype "power_in"))
      (node (ref "IC2") (pin "14") (pinfunction "VCC_14") (pintype "power_in"))
      (node (ref "IC3") (pin "14") (pinfunction "VCC_14") (pintype "power_in"))
      (node (ref "IC4") (pin "14") (pinfunction "VCC_14") (pintype "power_in"))
      (node (ref "IC5") (pin "10") (pinfunction "SCL_10") (pintype "input"))
      (node (ref "IC5") (pin "16") (pinfunction "VCC_16") (pintype "power_in"))
      (node (ref "IC6") (pin "10") (pinfunction "SCL_10") (pintype "input"))
      (node (ref "IC6") (pin "16") (pinfunction "VCC_16") (pintype "power_in"))
      (node (ref "IC7") (pin "10") (pinfunction "SCL_10") (pintype "input"))
      (node (ref "IC7") (pin "16") (pinfunction "VCC_16") (pintype "power_in"))
      (node (ref "IC8") (pin "10") (pinfunction "SCL_10") (pintype "input"))
      (node (ref "IC8") (pin "16") (pinfunction "VCC_16") (pintype "power_in"))
      (node (ref "INPUT1") (pin "10") (pinfunction "10_10") (pintype "passive"))
      (node (ref "INPUT2") (pin "10") (pinfunction "10_10") (pintype "passive"))
      (node (ref "LED1") (pin "A") (pinfunction "A_A") (pintype "passive"))
      (node (ref "OK1") (pin "2") (pinfunction "A_2") (pintype "passive"))
      (node (ref "OK2") (pin "8") (pinfunction "VCC_8") (pintype "passive"))
      (node (ref "OK3") (pin "8") (pinfunction "VCC_8") (pintype "passive"))
      (node (ref "OK4") (pin "8") (pinfunction "VCC_8") (pintype "passive"))
      (node (ref "OUTPUT1") (pin "10") (pinfunction "10_10") (pintype "passive"))
      (node (ref "OUTPUT2") (pin "10") (pinfunction "10_10") (pintype "passive"))
      (node (ref "R10") (pin "2") (pinfunction "2_2") (pintype "passive"))
      (node (ref "R11") (pin "2") (pinfunction "2_2") (pintype "passive"))
      (node (ref "R15") (pin "1") (pinfunction "1_1") (pintype "passive"))
      (node (ref "R9") (pin "2") (pinfunction "2_2") (pintype "passive"))
      (node (ref "RN1") (pin "1") (pinfunction "1_1") (pintype "passive"))
      (node (ref "RN4") (pin "1") (pinfunction "1_1") (pintype "passive"))
      (node (ref "V5") (pin "1") (pinfunction "1_1") (pintype "passive"))
    )
    (net (code "80") (name "Net-(IC1A-I1)") (class "Default")
      (node (ref "C-1") (pin "2") (pinfunction "2_2") (pintype "passive"))
      (node (ref "IC1") (pin "2") (pinfunction "I1_2") (pintype "input"))
    )
    (net (code "81") (name "Net-(IC1B-I1)") (class "Default")
      (node (ref "C-2") (pin "2") (pinfunction "2_2") (pintype "passive"))
      (node (ref "IC1") (pin "5") (pinfunction "I1_5") (pintype "input"))
    )
    (net (code "82") (name "Net-(IC1C-I1)") (class "Default")
      (node (ref "C-3") (pin "2") (pinfunction "2_2") (pintype "passive"))
      (node (ref "IC1") (pin "9") (pinfunction "I1_9") (pintype "input"))
    )
    (net (code "83") (name "Net-(IC1D-I1)") (class "Default")
      (node (ref "C2") (pin "2") (pinfunction "2_2") (pintype "passive"))
      (node (ref "IC1") (pin "12") (pinfunction "I1_12") (pintype "input"))
    )
    (net (code "84") (name "Net-(IC2A-I1)") (class "Default")
      (node (ref "C4") (pin "2") (pinfunction "2_2") (pintype "passive"))
      (node (ref "IC2") (pin "2") (pinfunction "I1_2") (pintype "input"))
    )
    (net (code "85") (name "Net-(IC2B-I1)") (class "Default")
      (node (ref "C3") (pin "2") (pinfunction "2_2") (pintype "passive"))
      (node (ref "IC2") (pin "5") (pinfunction "I1_5") (pintype "input"))
    )
    (net (code "86") (name "Net-(IC2C-I1)") (class "Default")
      (node (ref "C5") (pin "2") (pinfunction "2_2") (pintype "passive"))
      (node (ref "IC2") (pin "9") (pinfunction "I1_9") (pintype "input"))
    )
    (net (code "87") (name "Net-(IC2D-I1)") (class "Default")
      (node (ref "C6") (pin "2") (pinfunction "2_2") (pintype "passive"))
      (node (ref "IC2") (pin "12") (pinfunction "I1_12") (pintype "input"))
    )
    (net (code "88") (name "Net-(IC3A-I1)") (class "Default")
      (node (ref "C-10") (pin "2") (pinfunction "2_2") (pintype "passive"))
      (node (ref "IC3") (pin "2") (pinfunction "I1_2") (pintype "input"))
    )
    (net (code "89") (name "Net-(IC3B-I1)") (class "Default")
      (node (ref "C-11") (pin "2") (pinfunction "2_2") (pintype "passive"))
      (node (ref "IC3") (pin "5") (pinfunction "I1_5") (pintype "input"))
    )
    (net (code "90") (name "Net-(IC3C-I1)") (class "Default")
      (node (ref "C-12") (pin "2") (pinfunction "2_2") (pintype "passive"))
      (node (ref "IC3") (pin "9") (pinfunction "I1_9") (pintype "input"))
    )
    (net (code "91") (name "Net-(IC3D-I1)") (class "Default")
      (node (ref "C16") (pin "2") (pinfunction "2_2") (pintype "passive"))
      (node (ref "IC3") (pin "12") (pinfunction "I1_12") (pintype "input"))
    )
    (net (code "92") (name "Net-(IC4A-I1)") (class "Default")
      (node (ref "C1") (pin "2") (pinfunction "2_2") (pintype "passive"))
      (node (ref "IC4") (pin "2") (pinfunction "I1_2") (pintype "input"))
    )
    (net (code "93") (name "Net-(IC4B-I1)") (class "Default")
      (node (ref "C17") (pin "2") (pinfunction "2_2") (pintype "passive"))
      (node (ref "IC4") (pin "5") (pinfunction "I1_5") (pintype "input"))
    )
    (net (code "94") (name "Net-(IC4C-I1)") (class "Default")
      (node (ref "C9") (pin "2") (pinfunction "2_2") (pintype "passive"))
      (node (ref "IC4") (pin "9") (pinfunction "I1_9") (pintype "input"))
    )
    (net (code "95") (name "Net-(IC4D-I1)") (class "Default")
      (node (ref "C18") (pin "2") (pinfunction "2_2") (pintype "passive"))
      (node (ref "IC4") (pin "12") (pinfunction "I1_12") (pintype "input"))
    )
    (net (code "96") (name "Net-(IC9A-I0)") (class "Default")
      (node (ref "IC9") (pin "1") (pinfunction "I0_1") (pintype "input"))
      (node (ref "IC9") (pin "8") (pinfunction "O_8") (pintype "output"))
      (node (ref "R6") (pin "2") (pinfunction "2_2") (pintype "passive"))
    )
    (net (code "97") (name "Net-(IC9A-O)") (class "Default")
      (node (ref "IC9") (pin "3") (pinfunction "O_3") (pintype "output"))
      (node (ref "R2") (pin "2") (pinfunction "2_2") (pintype "passive"))
    )
    (net (code "98") (name "Net-(IC9B-O)") (class "Default")
      (node (ref "IC9") (pin "6") (pinfunction "O_6") (pintype "output"))
      (node (ref "R3") (pin "2") (pinfunction "2_2") (pintype "passive"))
    )
    (net (code "99") (name "Net-(IC9D-O)") (class "Default")
      (node (ref "IC9") (pin "11") (pinfunction "O_11") (pintype "output"))
      (node (ref "R1") (pin "2") (pinfunction "2_2") (pintype "passive"))
    )
    (net (code "100") (name "Net-(LED1-C)") (class "Default")
      (node (ref "LED1") (pin "K") (pinfunction "C_K") (pintype "passive"))
      (node (ref "R13") (pin "2") (pinfunction "2_2") (pintype "passive"))
    )
    (net (code "101") (name "Net-(LED2-C)") (class "Default")
      (node (ref "LED2") (pin "K") (pinfunction "C_K") (pintype "passive"))
      (node (ref "R12") (pin "2") (pinfunction "2_2") (pintype "passive"))
    )
    (net (code "102") (name "Net-(OK1-C)") (class "Default")
      (node (ref "OK1") (pin "3") (pinfunction "C_3") (pintype "passive"))
      (node (ref "R5") (pin "2") (pinfunction "2_2") (pintype "passive"))
    )
    (net (code "103") (name "Net-(OK2-C)") (class "Default")
      (node (ref "OK2") (pin "3") (pinfunction "C_3") (pintype "passive"))
      (node (ref "R3") (pin "1") (pinfunction "1_1") (pintype "passive"))
    )
    (net (code "104") (name "Net-(OK3-C)") (class "Default")
      (node (ref "OK3") (pin "3") (pinfunction "C_3") (pintype "passive"))
      (node (ref "R1") (pin "1") (pinfunction "1_1") (pintype "passive"))
    )
    (net (code "105") (name "Net-(OK4-C)") (class "Default")
      (node (ref "OK4") (pin "3") (pinfunction "C_3") (pintype "passive"))
      (node (ref "R2") (pin "1") (pinfunction "1_1") (pintype "passive"))
    )
    (net (code "106") (name "Net-(Q1-B)") (class "Default")
      (node (ref "C31") (pin "1") (pinfunction "1_1") (pintype "passive"))
      (node (ref "Q1") (pin "2") (pinfunction "B_2") (pintype "passive"))
      (node (ref "R14") (pin "2") (pinfunction "2_2") (pintype "passive"))
    )
    (net (code "107") (name "Net-(Q1-C)") (class "Default")
      (node (ref "Q1") (pin "3") (pinfunction "C_3") (pintype "passive"))
      (node (ref "R5") (pin "1") (pinfunction "1_1") (pintype "passive"))
    )
    (net (code "108") (name "Net-(Q2-B)") (class "Default")
      (node (ref "C30") (pin "2") (pinfunction "2_2") (pintype "passive"))
      (node (ref "Q2") (pin "2") (pinfunction "B_2") (pintype "passive"))
      (node (ref "R16") (pin "1") (pinfunction "1_1") (pintype "passive"))
    )
    (net (code "109") (name "unconnected-(5V-Pad2)") (class "Default")
      (node (ref "5V") (pin "2") (pinfunction "2_2") (pintype "passive"))
    )
    (net (code "110") (name "unconnected-(5V-Pad3)") (class "Default")
      (node (ref "5V") (pin "3") (pinfunction "3_3") (pintype "passive"))
    )
    (net (code "111") (name "unconnected-(IC5A-SER-Pad14)") (class "Default")
      (node (ref "IC5") (pin "14") (pinfunction "SER_14") (pintype "input"))
    )
    (net (code "112") (name "unconnected-(IC8A-QH*-Pad9)") (class "Default")
      (node (ref "IC8") (pin "9") (pinfunction "QH*_9") (pintype "tri_state"))
    )
    (net (code "113") (name "unconnected-(IC9A-I1-Pad2)") (class "Default")
      (node (ref "IC9") (pin "2") (pinfunction "I1_2") (pintype "input"))
    )
    (net (code "114") (name "unconnected-(IC9B-I1-Pad5)") (class "Default")
      (node (ref "IC9") (pin "5") (pinfunction "I1_5") (pintype "input"))
    )
    (net (code "115") (name "unconnected-(IC9C-I1-Pad9)") (class "Default")
      (node (ref "IC9") (pin "9") (pinfunction "I1_9") (pintype "input"))
    )
    (net (code "116") (name "unconnected-(IC9D-I1-Pad12)") (class "Default")
      (node (ref "IC9") (pin "12") (pinfunction "I1_12") (pintype "input"))
    )
    (net (code "117") (name "unconnected-(OK1-VE-Pad7)") (class "Default")
      (node (ref "OK1") (pin "7") (pinfunction "VE_7") (pintype "passive"))
    )
    (net (code "118") (name "unconnected-(OK2-VE-Pad7)") (class "Default")
      (node (ref "OK2") (pin "7") (pinfunction "VE_7") (pintype "passive"))
    )
    (net (code "119") (name "unconnected-(OK3-VE-Pad7)") (class "Default")
      (node (ref "OK3") (pin "7") (pinfunction "VE_7") (pintype "passive"))
    )
    (net (code "120") (name "unconnected-(OK4-VE-Pad7)") (class "Default")
      (node (ref "OK4") (pin "7") (pinfunction "VE_7") (pintype "passive"))
    )
  )
)
